# MCU_1.net
KiCad netlist of a schematic drawn in Altium Designer
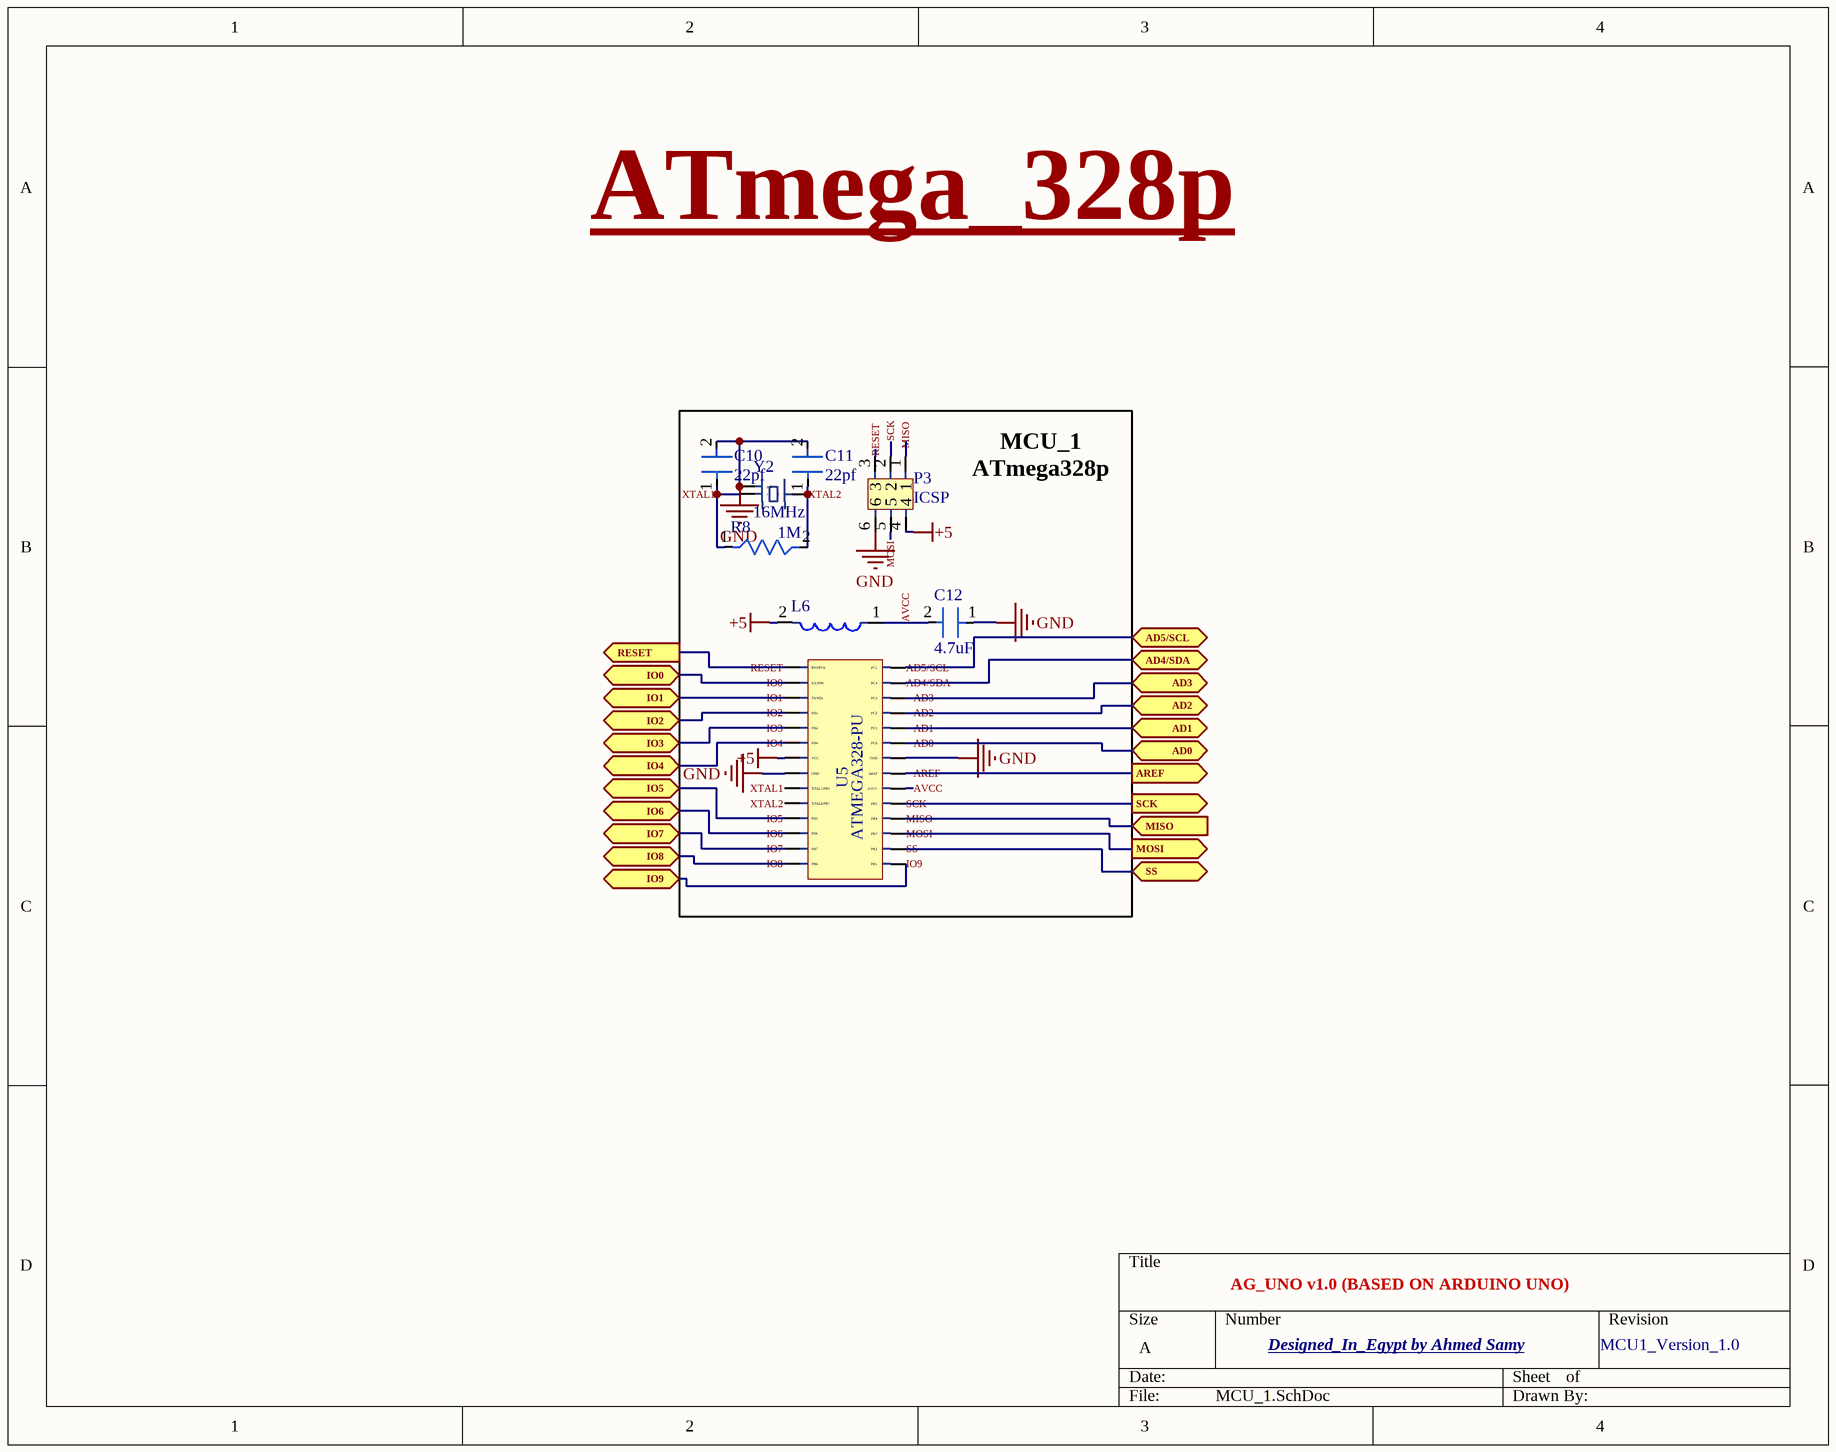
[diagram p0: MCU_1.SchDoc]

(export (version "E")
  (design (tool "Eeschema 10.0.6"))
  (components
    (comp (ref "C10")
      (value "22pf")
      (footprint "3372-0805W475K500CCTR-ND")
      (description "CAP.,SMD,0805,X5R,4.7UF,10%,50V")
      (libsource (lib "Task") (part "3372-0805W475K500CCTR-ND"))
    )
    (comp (ref "C11")
      (value "22pf")
      (footprint "3372-0805W475K500CCTR-ND")
      (description "CAP.,SMD,0805,X5R,4.7UF,10%,50V")
      (libsource (lib "Task") (part "3372-0805W475K500CCTR-ND"))
    )
    (comp (ref "C12")
      (value "4.7uF")
      (footprint "3372-0805W475K500CCTR-ND")
      (description "CAP.,SMD,0805,X5R,4.7UF,10%,50V")
      (libsource (lib "Task") (part "3372-0805W475K500CCTR-ND"))
    )
    (comp (ref "L6")
      (value "CV201210-100K")
      (footprint "CV201210-100K")
      (description "10 µH Shielded Multilayer Inductor 15 mA 1.15Ohm Max 0805 (2012 Metric)")
      (libsource (lib "Task") (part "CV201210-100K"))
    )
    (comp (ref "P3")
      (value "ICSP")
      (footprint "PH2-06-UA")
      (description "Connector Header Through Hole 6 position 0.100\" (2.54mm) [ICSP UNO]")
      (libsource (lib "Task") (part "PH2-06-UA"))
    )
    (comp (ref "R8")
      (value "1M")
      (footprint "CRCW06031M00JNEAC")
      (description "1 MOhms ±5% 0.1W, 1/10W Chip Resistor 0603 (1608 Metric) Thick Film")
      (libsource (lib "Task") (part "CRCW06031M00JNEAC"))
    )
    (comp (ref "U5")
      (value "ATMEGA328-PU")
      (footprint "ATMEGA328-PU")
      (description "AVR AVR® ATmega Microcontroller IC 8-Bit 20MHz 32KB (16K x 16) FLASH 28-PDIP")
      (libsource (lib "Task") (part "ATMEGA328-PU"))
    )
    (comp (ref "Y2")
      (value "16MHz")
      (footprint "CSTCE16M0V53-R0")
      (description "16 MHz Ceramic Resonator Built in Capacitor 15 pF ±0.3% -20°C ~ 80°C Surface Mount")
      (libsource (lib "Task") (part "CSTCE16M0V53-R0"))
    )
  )
  (nets
    (net (code "1") (name "+5") (class "Default")
      (node (ref "L6") (pin "2") (pinfunction "2_2") (pintype "passive"))
      (node (ref "P3") (pin "4") (pinfunction "4_4") (pintype "passive"))
      (node (ref "U5") (pin "7") (pinfunction "VCC_7") (pintype "passive"))
    )
    (net (code "2") (name "/AD0") (class "Default")
      (node (ref "U5") (pin "23") (pinfunction "PC0_23") (pintype "bidirectional"))
    )
    (net (code "3") (name "/AD1") (class "Default")
      (node (ref "U5") (pin "24") (pinfunction "PC1_24") (pintype "bidirectional"))
    )
    (net (code "4") (name "/AD2") (class "Default")
      (node (ref "U5") (pin "25") (pinfunction "PC2_25") (pintype "bidirectional"))
    )
    (net (code "5") (name "/AD3") (class "Default")
      (node (ref "U5") (pin "26") (pinfunction "PC3_26") (pintype "bidirectional"))
    )
    (net (code "6") (name "/AD4{slash}SDA") (class "Default")
      (node (ref "U5") (pin "27") (pinfunction "PC4_27") (pintype "bidirectional"))
    )
    (net (code "7") (name "/AD5{slash}SCL") (class "Default")
      (node (ref "U5") (pin "28") (pinfunction "PC5_28") (pintype "bidirectional"))
    )
    (net (code "8") (name "/AREF") (class "Default")
      (node (ref "U5") (pin "21") (pinfunction "AREF_21") (pintype "input"))
    )
    (net (code "9") (name "/AVCC") (class "Default")
      (node (ref "C12") (pin "2") (pintype "passive"))
      (node (ref "L6") (pin "1") (pinfunction "1_1") (pintype "passive"))
      (node (ref "U5") (pin "20") (pinfunction "AVCC_20") (pintype "power_in"))
    )
    (net (code "10") (name "/IO0") (class "Default")
      (node (ref "U5") (pin "2") (pinfunction "RX/PD0_2") (pintype "bidirectional"))
    )
    (net (code "11") (name "/IO1") (class "Default")
      (node (ref "U5") (pin "3") (pinfunction "TX/PD1_3") (pintype "bidirectional"))
    )
    (net (code "12") (name "/IO2") (class "Default")
      (node (ref "U5") (pin "4") (pinfunction "PD2_4") (pintype "bidirectional"))
    )
    (net (code "13") (name "/IO3") (class "Default")
      (node (ref "U5") (pin "5") (pinfunction "PD3_5") (pintype "bidirectional"))
    )
    (net (code "14") (name "/IO4") (class "Default")
      (node (ref "U5") (pin "6") (pinfunction "PD4_6") (pintype "bidirectional"))
    )
    (net (code "15") (name "/IO5") (class "Default")
      (node (ref "U5") (pin "11") (pinfunction "PD5_11") (pintype "bidirectional"))
    )
    (net (code "16") (name "/IO6") (class "Default")
      (node (ref "U5") (pin "12") (pinfunction "PD6_12") (pintype "bidirectional"))
    )
    (net (code "17") (name "/IO7") (class "Default")
      (node (ref "U5") (pin "13") (pinfunction "PD7_13") (pintype "bidirectional"))
    )
    (net (code "18") (name "/IO8") (class "Default")
      (node (ref "U5") (pin "14") (pinfunction "PB0_14") (pintype "bidirectional"))
    )
    (net (code "19") (name "/IO9") (class "Default")
      (node (ref "U5") (pin "15") (pinfunction "PB1_15") (pintype "bidirectional"))
    )
    (net (code "20") (name "/MISO") (class "Default")
      (node (ref "P3") (pin "1") (pinfunction "1_1") (pintype "passive"))
      (node (ref "U5") (pin "18") (pinfunction "PB4_18") (pintype "bidirectional"))
    )
    (net (code "21") (name "/MOSI") (class "Default")
      (node (ref "P3") (pin "5") (pinfunction "5_5") (pintype "passive"))
      (node (ref "U5") (pin "17") (pinfunction "PB3_17") (pintype "bidirectional"))
    )
    (net (code "22") (name "/RESET") (class "Default")
      (node (ref "P3") (pin "3") (pinfunction "3_3") (pintype "passive"))
      (node (ref "U5") (pin "1") (pinfunction "RST/PC6_1") (pintype "bidirectional"))
    )
    (net (code "23") (name "/SCK") (class "Default")
      (node (ref "P3") (pin "2") (pinfunction "2_2") (pintype "passive"))
      (node (ref "U5") (pin "19") (pinfunction "PB5_19") (pintype "bidirectional"))
    )
    (net (code "24") (name "/SS") (class "Default")
      (node (ref "U5") (pin "16") (pinfunction "PB2_16") (pintype "bidirectional"))
    )
    (net (code "25") (name "/XTAL1") (class "Default")
      (node (ref "C10") (pin "1") (pintype "passive"))
      (node (ref "R8") (pin "1") (pinfunction "1_1") (pintype "passive"))
      (node (ref "U5") (pin "9") (pinfunction "XTAL1/PB6_9") (pintype "bidirectional"))
      (node (ref "Y2") (pin "1") (pinfunction "1_1") (pintype "passive"))
    )
    (net (code "26") (name "/XTAL2") (class "Default")
      (node (ref "C11") (pin "1") (pintype "passive"))
      (node (ref "R8") (pin "2") (pinfunction "2_2") (pintype "passive"))
      (node (ref "U5") (pin "10") (pinfunction "XTAL2/PB7_10") (pintype "bidirectional"))
      (node (ref "Y2") (pin "3") (pinfunction "3_3") (pintype "passive"))
    )
    (net (code "27") (name "GND") (class "Default")
      (node (ref "C10") (pin "2") (pintype "passive"))
      (node (ref "C11") (pin "2") (pintype "passive"))
      (node (ref "C12") (pin "1") (pintype "passive"))
      (node (ref "P3") (pin "6") (pinfunction "6_6") (pintype "passive"))
      (node (ref "U5") (pin "22") (pinfunction "GND_22") (pintype "power_in"))
      (node (ref "U5") (pin "8") (pinfunction "GND_8") (pintype "power_in"))
      (node (ref "Y2") (pin "2") (pinfunction "gnd_2") (pintype "power_in"))
    )
  )
)
